# EC3simple.net
KiCad netlist of a schematic drawn in Altium Designer
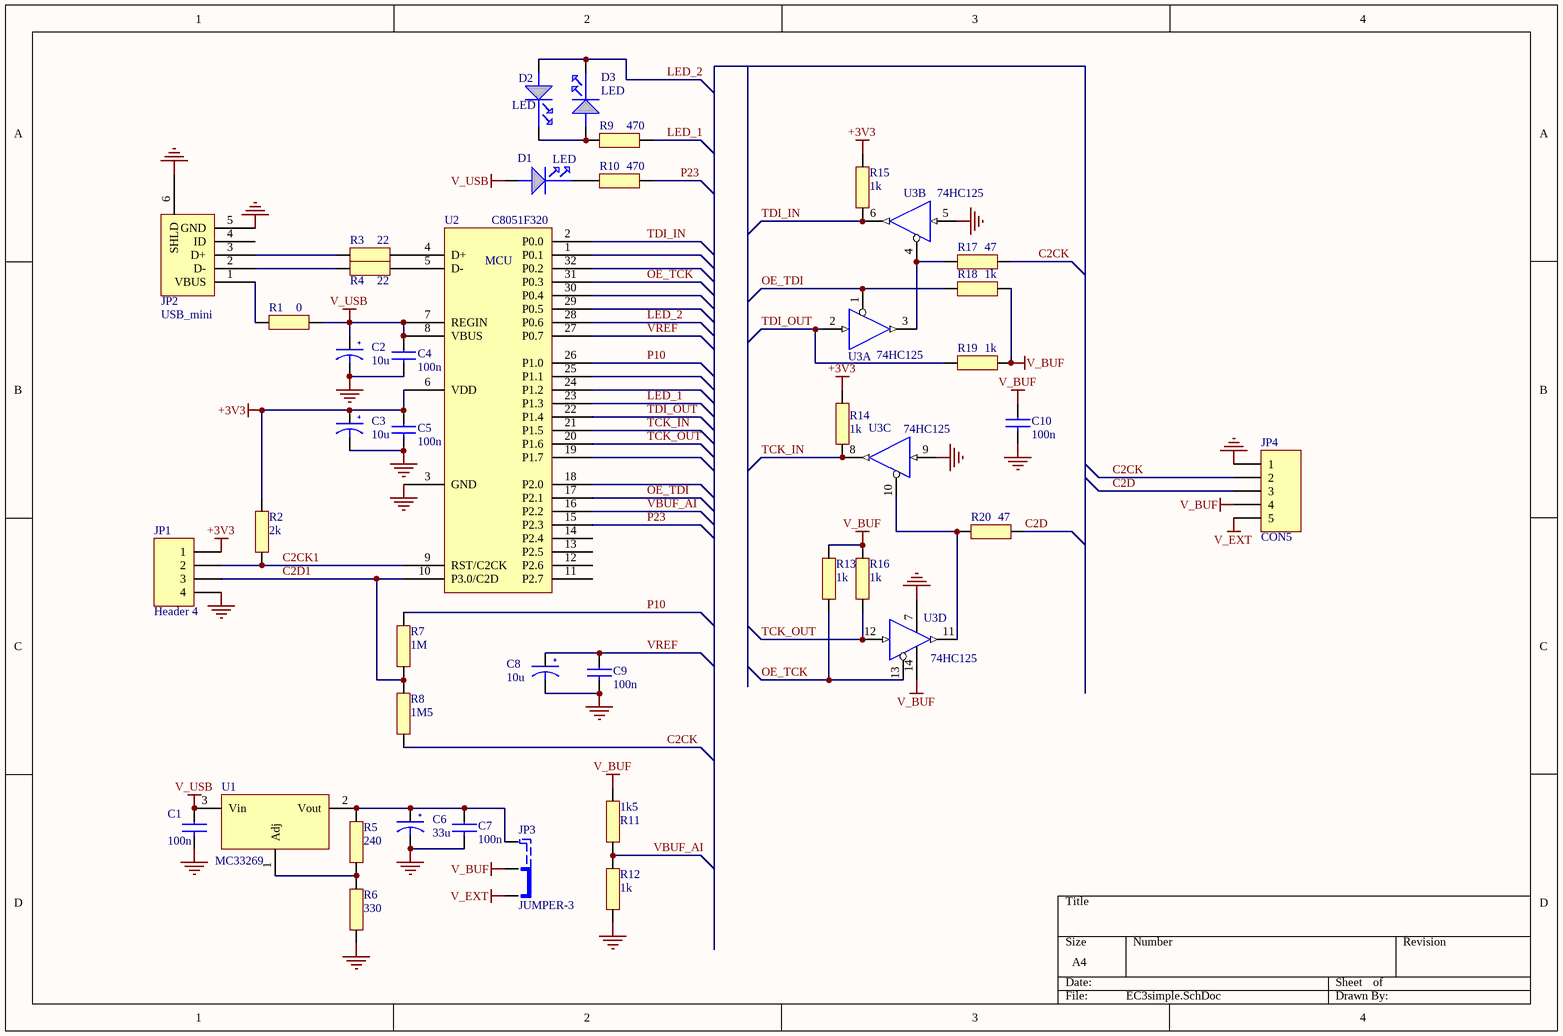
[diagram p0: EC3simple.SchDoc]

(export (version "E")
  (design (tool "Eeschema 10.0.6"))
  (components
    (comp (ref "C1") (value "100n") (footprint "C-0805") (libsource (lib "RCS-Discret") (part "C")))
    (comp (ref "C2") (value "10u") (footprint "TANTAL-A") (libsource (lib "RCS-Discret") (part "C-EL-TAN")))
    (comp (ref "C3") (value "10u") (footprint "TANTAL-A") (libsource (lib "RCS-Discret") (part "C-EL-TAN")))
    (comp (ref "C4") (value "100n") (footprint "C-0805") (libsource (lib "RCS-Discret") (part "C")))
    (comp (ref "C5") (value "100n") (footprint "C-0805") (libsource (lib "RCS-Discret") (part "C")))
    (comp (ref "C6")
      (value "33u")
      (footprint "TANTAL-B(3528)")
      (libsource (lib "RCS-Discret") (part "C-EL-TAN"))
    )
    (comp (ref "C7") (value "100n") (footprint "C-0805") (libsource (lib "RCS-Discret") (part "C")))
    (comp (ref "C8") (value "10u") (footprint "TANTAL-A") (libsource (lib "RCS-Discret") (part "C-EL-TAN")))
    (comp (ref "C9") (value "100n") (footprint "C-0805") (libsource (lib "RCS-Discret") (part "C")))
    (comp (ref "C10") (value "100n") (footprint "C-0805") (libsource (lib "RCS-Discret") (part "C")))
    (comp (ref "D1") (value "LED") (footprint "LED-DIP-1") (libsource (lib "RCS-Discret") (part "LED")))
    (comp (ref "D2") (value "LED") (footprint "LED-DIP-1") (libsource (lib "RCS-Discret") (part "LED")))
    (comp (ref "D3") (value "LED") (footprint "LED-DIP-1") (libsource (lib "RCS-Discret") (part "LED")))
    (comp (ref "JP1")
      (value "Header 4")
      (footprint "HDR1X4")
      (description "Header, 4-Pin")
      (fields (field (name "PUBLISHER") "Altium Limited"))
      (libsource (lib "Miscellaneous Connectors") (part "Header 4"))
    )
    (comp (ref "JP2")
      (value "USB_mini")
      (footprint "miniUSBsmd")
      (libsource (lib "ISPMKII") (part "USB_mini"))
    )
    (comp (ref "JP3")
      (value "JUMPER-3")
      (footprint "IDC1-3P")
      (description "Jumper")
      (libsource (lib "RCS-Connect&pushe") (part "JUMPER-3"))
    )
    (comp (ref "JP4")
      (value "CON5")
      (footprint "IDC1-5P")
      (libsource (lib "RCS-Connect&pushe") (part "CON5"))
    )
    (comp (ref "R1") (value "0") (footprint "R-1206") (libsource (lib "RCS-Discret") (part "R")))
    (comp (ref "R2") (value "2k") (footprint "R-0805") (libsource (lib "") (part "R_1")))
    (comp (ref "R3") (value "22") (footprint "R-0805") (libsource (lib "RCS-Discret") (part "R")))
    (comp (ref "R4") (value "22") (footprint "R-0805") (libsource (lib "RCS-Discret") (part "R")))
    (comp (ref "R5") (value "240") (footprint "R-0805") (libsource (lib "") (part "R_1")))
    (comp (ref "R6") (value "330") (footprint "R-0805") (libsource (lib "") (part "R_1")))
    (comp (ref "R7") (value "1M") (footprint "R-0805") (libsource (lib "") (part "R_1")))
    (comp (ref "R8") (value "1M5") (footprint "R-0805") (libsource (lib "") (part "R_1")))
    (comp (ref "R9") (value "470") (footprint "R-0805") (libsource (lib "RCS-Discret") (part "R")))
    (comp (ref "R10") (value "470") (footprint "R-0805") (libsource (lib "RCS-Discret") (part "R")))
    (comp (ref "R11") (value "1k5") (footprint "R-0805") (libsource (lib "") (part "R_1")))
    (comp (ref "R12") (value "1k") (footprint "R-0805") (libsource (lib "") (part "R_1")))
    (comp (ref "R13") (value "1k") (footprint "R-0805") (libsource (lib "") (part "R_1")))
    (comp (ref "R14") (value "1k") (footprint "R-0805") (libsource (lib "") (part "R_1")))
    (comp (ref "R15") (value "1k") (footprint "R-0805") (libsource (lib "") (part "R_1")))
    (comp (ref "R16") (value "1k") (footprint "R-0805") (libsource (lib "") (part "R_1")))
    (comp (ref "R17") (value "47") (footprint "R-0805") (libsource (lib "RCS-Discret") (part "R")))
    (comp (ref "R18") (value "1k") (footprint "R-0805") (libsource (lib "RCS-Discret") (part "R")))
    (comp (ref "R19") (value "1k") (footprint "R-0805") (libsource (lib "RCS-Discret") (part "R")))
    (comp (ref "R20") (value "47") (footprint "R-0805") (libsource (lib "RCS-Discret") (part "R")))
    (comp (ref "U1")
      (value "MC33269")
      (footprint "SOT-428-(D-PAK)")
      (description "low dropout adjustable positive voltage regulators")
      (libsource (lib "RCS-IMS") (part "MC33269"))
    )
    (comp (ref "U2") (value "C8051F320") (footprint "QFP32") (libsource (lib "RCS-IMS") (part "C8051F320")))
    (comp (ref "U3")
      (value "74HC125")
      (footprint "SO14-(SOT-108-1)")
      (description "Four Buffers with Enable for HiZ state output")
      (libsource (lib "RCS-IMS") (part "74HC125"))
    )
  )
  (nets
    (net (code "1") (name "+3V3") (class "Default")
      (node (ref "C3") (pin "2") (pinfunction "+_2") (pintype "passive"))
      (node (ref "C5") (pin "1") (pinfunction "1_1") (pintype "passive"))
      (node (ref "JP1") (pin "1") (pinfunction "1_1") (pintype "passive"))
      (node (ref "R14") (pin "1") (pinfunction "1_1") (pintype "passive"))
      (node (ref "R15") (pin "1") (pinfunction "1_1") (pintype "passive"))
      (node (ref "R2") (pin "1") (pinfunction "1_1") (pintype "passive"))
      (node (ref "U2") (pin "6") (pinfunction "VDD_6") (pintype "passive"))
    )
    (net (code "2") (name "/C2CK") (class "Default")
      (node (ref "JP4") (pin "2") (pinfunction "2_2") (pintype "passive"))
      (node (ref "R17") (pin "2") (pinfunction "2_2") (pintype "passive"))
      (node (ref "R8") (pin "2") (pinfunction "2_2") (pintype "passive"))
    )
    (net (code "3") (name "/C2CK1") (class "Default")
      (node (ref "JP1") (pin "2") (pinfunction "2_2") (pintype "passive"))
      (node (ref "R2") (pin "2") (pinfunction "2_2") (pintype "passive"))
      (node (ref "U2") (pin "9") (pinfunction "RST/C2CK_9") (pintype "passive"))
    )
    (net (code "4") (name "/C2D") (class "Default")
      (node (ref "JP4") (pin "3") (pinfunction "3_3") (pintype "passive"))
      (node (ref "R20") (pin "2") (pinfunction "2_2") (pintype "passive"))
    )
    (net (code "5") (name "/C2D1") (class "Default")
      (node (ref "JP1") (pin "3") (pinfunction "3_3") (pintype "passive"))
      (node (ref "R7") (pin "2") (pinfunction "2_2") (pintype "passive"))
      (node (ref "R8") (pin "1") (pinfunction "1_1") (pintype "passive"))
      (node (ref "U2") (pin "10") (pinfunction "P3.0/C2D_10") (pintype "passive"))
    )
    (net (code "6") (name "/LED_1") (class "Default")
      (node (ref "R9") (pin "2") (pinfunction "2_2") (pintype "passive"))
      (node (ref "U2") (pin "23") (pinfunction "P1.3_23") (pintype "passive"))
    )
    (net (code "7") (name "/LED_2") (class "Default")
      (node (ref "D2") (pin "A") (pinfunction "ANODE_A") (pintype "passive"))
      (node (ref "D3") (pin "K") (pinfunction "CATHODE_K") (pintype "passive"))
      (node (ref "U2") (pin "28") (pinfunction "P0.6_28") (pintype "passive"))
    )
    (net (code "8") (name "/OE_TCK") (class "Default")
      (node (ref "R13") (pin "2") (pinfunction "2_2") (pintype "passive"))
      (node (ref "U2") (pin "31") (pinfunction "P0.3_31") (pintype "passive"))
      (node (ref "U3") (pin "13") (pinfunction "~{-Ed}_13") (pintype "passive"))
    )
    (net (code "9") (name "/OE_TDI") (class "Default")
      (node (ref "R18") (pin "1") (pinfunction "1_1") (pintype "passive"))
      (node (ref "U2") (pin "17") (pinfunction "P2.1_17") (pintype "passive"))
      (node (ref "U3") (pin "1") (pinfunction "~{-Ea}_1") (pintype "passive"))
    )
    (net (code "10") (name "/P10") (class "Default")
      (node (ref "R7") (pin "1") (pinfunction "1_1") (pintype "passive"))
      (node (ref "U2") (pin "26") (pinfunction "P1.0_26") (pintype "passive"))
    )
    (net (code "11") (name "/P23") (class "Default")
      (node (ref "R10") (pin "2") (pinfunction "2_2") (pintype "passive"))
      (node (ref "U2") (pin "15") (pinfunction "P2.3_15") (pintype "passive"))
    )
    (net (code "12") (name "/TCK_IN") (class "Default")
      (node (ref "R14") (pin "2") (pinfunction "2_2") (pintype "passive"))
      (node (ref "U2") (pin "21") (pinfunction "P1.5_21") (pintype "passive"))
      (node (ref "U3") (pin "8") (pinfunction "Yc_8") (pintype "output"))
    )
    (net (code "13") (name "/TCK_OUT") (class "Default")
      (node (ref "R16") (pin "2") (pinfunction "2_2") (pintype "passive"))
      (node (ref "U2") (pin "20") (pinfunction "P1.6_20") (pintype "passive"))
      (node (ref "U3") (pin "12") (pinfunction "D_12") (pintype "input"))
    )
    (net (code "14") (name "/TDI_IN") (class "Default")
      (node (ref "R15") (pin "2") (pinfunction "2_2") (pintype "passive"))
      (node (ref "U2") (pin "2") (pinfunction "P0.0_2") (pintype "passive"))
      (node (ref "U3") (pin "6") (pinfunction "Yb_6") (pintype "output"))
    )
    (net (code "15") (name "/TDI_OUT") (class "Default")
      (node (ref "R19") (pin "1") (pinfunction "1_1") (pintype "passive"))
      (node (ref "U2") (pin "22") (pinfunction "P1.4_22") (pintype "passive"))
      (node (ref "U3") (pin "2") (pinfunction "A_2") (pintype "input"))
    )
    (net (code "16") (name "/VBUF_AI") (class "Default")
      (node (ref "R11") (pin "2") (pinfunction "2_2") (pintype "passive"))
      (node (ref "R12") (pin "1") (pinfunction "1_1") (pintype "passive"))
      (node (ref "U2") (pin "16") (pinfunction "P2.2_16") (pintype "passive"))
    )
    (net (code "17") (name "/VREF") (class "Default")
      (node (ref "C8") (pin "2") (pinfunction "+_2") (pintype "passive"))
      (node (ref "C9") (pin "1") (pinfunction "1_1") (pintype "passive"))
      (node (ref "U2") (pin "27") (pinfunction "P0.7_27") (pintype "passive"))
    )
    (net (code "18") (name "GND") (class "Default")
      (node (ref "C1") (pin "2") (pinfunction "2_2") (pintype "passive"))
      (node (ref "C10") (pin "2") (pinfunction "2_2") (pintype "passive"))
      (node (ref "C2") (pin "1") (pinfunction "-_1") (pintype "passive"))
      (node (ref "C3") (pin "1") (pinfunction "-_1") (pintype "passive"))
      (node (ref "C4") (pin "2") (pinfunction "2_2") (pintype "passive"))
      (node (ref "C5") (pin "2") (pinfunction "2_2") (pintype "passive"))
      (node (ref "C6") (pin "1") (pinfunction "-_1") (pintype "passive"))
      (node (ref "C7") (pin "2") (pinfunction "2_2") (pintype "passive"))
      (node (ref "C8") (pin "1") (pinfunction "-_1") (pintype "passive"))
      (node (ref "C9") (pin "2") (pinfunction "2_2") (pintype "passive"))
      (node (ref "JP1") (pin "4") (pinfunction "4_4") (pintype "passive"))
      (node (ref "JP2") (pin "5") (pinfunction "GND_5") (pintype "passive"))
      (node (ref "JP2") (pin "6") (pinfunction "SHLD_6") (pintype "passive"))
      (node (ref "JP4") (pin "1") (pinfunction "1_1") (pintype "passive"))
      (node (ref "R12") (pin "2") (pinfunction "2_2") (pintype "passive"))
      (node (ref "R6") (pin "2") (pinfunction "2_2") (pintype "passive"))
      (node (ref "U2") (pin "3") (pinfunction "GND_3") (pintype "passive"))
      (node (ref "U3") (pin "5") (pinfunction "B_5") (pintype "input"))
      (node (ref "U3") (pin "7") (pinfunction "GND-D_7") (pintype "power_in"))
      (node (ref "U3") (pin "9") (pinfunction "C_9") (pintype "input"))
    )
    (net (code "19") (name "Net-(C6-+)") (class "Default")
      (node (ref "C6") (pin "2") (pinfunction "+_2") (pintype "passive"))
      (node (ref "C7") (pin "1") (pinfunction "1_1") (pintype "passive"))
      (node (ref "JP3") (pin "3") (pinfunction "3_3") (pintype "passive"))
      (node (ref "R5") (pin "1") (pinfunction "1_1") (pintype "passive"))
      (node (ref "U1") (pin "2") (pinfunction "Vout_2") (pintype "passive"))
    )
    (net (code "20") (name "Net-(D1-CATHODE)") (class "Default")
      (node (ref "D1") (pin "K") (pinfunction "CATHODE_K") (pintype "passive"))
      (node (ref "R10") (pin "1") (pinfunction "1_1") (pintype "passive"))
    )
    (net (code "21") (name "Net-(D2-CATHODE)") (class "Default")
      (node (ref "D2") (pin "K") (pinfunction "CATHODE_K") (pintype "passive"))
      (node (ref "D3") (pin "A") (pinfunction "ANODE_A") (pintype "passive"))
      (node (ref "R9") (pin "1") (pinfunction "1_1") (pintype "passive"))
    )
    (net (code "22") (name "Net-(JP2-D+)") (class "Default")
      (node (ref "JP2") (pin "3") (pinfunction "D+_3") (pintype "passive"))
      (node (ref "R3") (pin "1") (pinfunction "1_1") (pintype "passive"))
    )
    (net (code "23") (name "Net-(JP2-D-)") (class "Default")
      (node (ref "JP2") (pin "2") (pinfunction "D-_2") (pintype "passive"))
      (node (ref "R4") (pin "1") (pinfunction "1_1") (pintype "passive"))
    )
    (net (code "24") (name "Net-(JP2-VBUS)") (class "Default")
      (node (ref "JP2") (pin "1") (pinfunction "VBUS_1") (pintype "passive"))
      (node (ref "R1") (pin "1") (pinfunction "1_1") (pintype "passive"))
    )
    (net (code "25") (name "Net-(U1-Adj)") (class "Default")
      (node (ref "R5") (pin "2") (pinfunction "2_2") (pintype "passive"))
      (node (ref "R6") (pin "1") (pinfunction "1_1") (pintype "passive"))
      (node (ref "U1") (pin "1") (pinfunction "Adj_1") (pintype "passive"))
    )
    (net (code "26") (name "Net-(U2-D+)") (class "Default")
      (node (ref "R3") (pin "2") (pinfunction "2_2") (pintype "passive"))
      (node (ref "U2") (pin "4") (pinfunction "D+_4") (pintype "passive"))
    )
    (net (code "27") (name "Net-(U2-D-)") (class "Default")
      (node (ref "R4") (pin "2") (pinfunction "2_2") (pintype "passive"))
      (node (ref "U2") (pin "5") (pinfunction "D-_5") (pintype "passive"))
    )
    (net (code "28") (name "Net-(U3A-Ya)") (class "Default")
      (node (ref "R17") (pin "1") (pinfunction "1_1") (pintype "passive"))
      (node (ref "U3") (pin "3") (pinfunction "Ya_3") (pintype "output"))
      (node (ref "U3") (pin "4") (pinfunction "~{-Eb}_4") (pintype "passive"))
    )
    (net (code "29") (name "Net-(U3C-~{-Ec})") (class "Default")
      (node (ref "R20") (pin "1") (pinfunction "1_1") (pintype "passive"))
      (node (ref "U3") (pin "10") (pinfunction "~{-Ec}_10") (pintype "passive"))
      (node (ref "U3") (pin "11") (pinfunction "Yd_11") (pintype "output"))
    )
    (net (code "30") (name "V_BUF") (class "Default")
      (node (ref "C10") (pin "1") (pinfunction "1_1") (pintype "passive"))
      (node (ref "JP3") (pin "2") (pinfunction "2_2") (pintype "passive"))
      (node (ref "JP4") (pin "4") (pinfunction "4_4") (pintype "passive"))
      (node (ref "R11") (pin "1") (pinfunction "1_1") (pintype "passive"))
      (node (ref "R13") (pin "1") (pinfunction "1_1") (pintype "passive"))
      (node (ref "R16") (pin "1") (pinfunction "1_1") (pintype "passive"))
      (node (ref "R18") (pin "2") (pinfunction "2_2") (pintype "passive"))
      (node (ref "R19") (pin "2") (pinfunction "2_2") (pintype "passive"))
      (node (ref "U3") (pin "14") (pinfunction "VCC_14") (pintype "power_in"))
    )
    (net (code "31") (name "V_EXT") (class "Default")
      (node (ref "JP3") (pin "1") (pinfunction "1_1") (pintype "passive"))
      (node (ref "JP4") (pin "5") (pinfunction "5_5") (pintype "passive"))
    )
    (net (code "32") (name "V_USB") (class "Default")
      (node (ref "C1") (pin "1") (pinfunction "1_1") (pintype "passive"))
      (node (ref "C2") (pin "2") (pinfunction "+_2") (pintype "passive"))
      (node (ref "C4") (pin "1") (pinfunction "1_1") (pintype "passive"))
      (node (ref "D1") (pin "A") (pinfunction "ANODE_A") (pintype "passive"))
      (node (ref "R1") (pin "2") (pinfunction "2_2") (pintype "passive"))
      (node (ref "U1") (pin "3") (pinfunction "Vin_3") (pintype "passive"))
      (node (ref "U2") (pin "7") (pinfunction "REGIN_7") (pintype "passive"))
      (node (ref "U2") (pin "8") (pinfunction "VBUS_8") (pintype "passive"))
    )
    (net (code "33") (name "unconnected-(JP2-ID-Pad4)") (class "Default")
      (node (ref "JP2") (pin "4") (pinfunction "ID_4") (pintype "passive"))
    )
    (net (code "34") (name "unconnected-(U2-P0.1-Pad1)") (class "Default")
      (node (ref "U2") (pin "1") (pinfunction "P0.1_1") (pintype "passive"))
    )
    (net (code "35") (name "unconnected-(U2-P0.2-Pad32)") (class "Default")
      (node (ref "U2") (pin "32") (pinfunction "P0.2_32") (pintype "passive"))
    )
    (net (code "36") (name "unconnected-(U2-P0.4-Pad30)") (class "Default")
      (node (ref "U2") (pin "30") (pinfunction "P0.4_30") (pintype "passive"))
    )
    (net (code "37") (name "unconnected-(U2-P0.5-Pad29)") (class "Default")
      (node (ref "U2") (pin "29") (pinfunction "P0.5_29") (pintype "passive"))
    )
    (net (code "38") (name "unconnected-(U2-P1.1-Pad25)") (class "Default")
      (node (ref "U2") (pin "25") (pinfunction "P1.1_25") (pintype "passive"))
    )
    (net (code "39") (name "unconnected-(U2-P1.2-Pad24)") (class "Default")
      (node (ref "U2") (pin "24") (pinfunction "P1.2_24") (pintype "passive"))
    )
    (net (code "40") (name "unconnected-(U2-P1.7-Pad19)") (class "Default")
      (node (ref "U2") (pin "19") (pinfunction "P1.7_19") (pintype "passive"))
    )
    (net (code "41") (name "unconnected-(U2-P2.0-Pad18)") (class "Default")
      (node (ref "U2") (pin "18") (pinfunction "P2.0_18") (pintype "passive"))
    )
    (net (code "42") (name "unconnected-(U2-P2.4-Pad14)") (class "Default")
      (node (ref "U2") (pin "14") (pinfunction "P2.4_14") (pintype "passive"))
    )
    (net (code "43") (name "unconnected-(U2-P2.5-Pad13)") (class "Default")
      (node (ref "U2") (pin "13") (pinfunction "P2.5_13") (pintype "passive"))
    )
    (net (code "44") (name "unconnected-(U2-P2.6-Pad12)") (class "Default")
      (node (ref "U2") (pin "12") (pinfunction "P2.6_12") (pintype "passive"))
    )
    (net (code "45") (name "unconnected-(U2-P2.7-Pad11)") (class "Default")
      (node (ref "U2") (pin "11") (pinfunction "P2.7_11") (pintype "passive"))
    )
  )
)
